# 01-pushbutton_interface.net
KiCad netlist of a schematic drawn in EAGLE
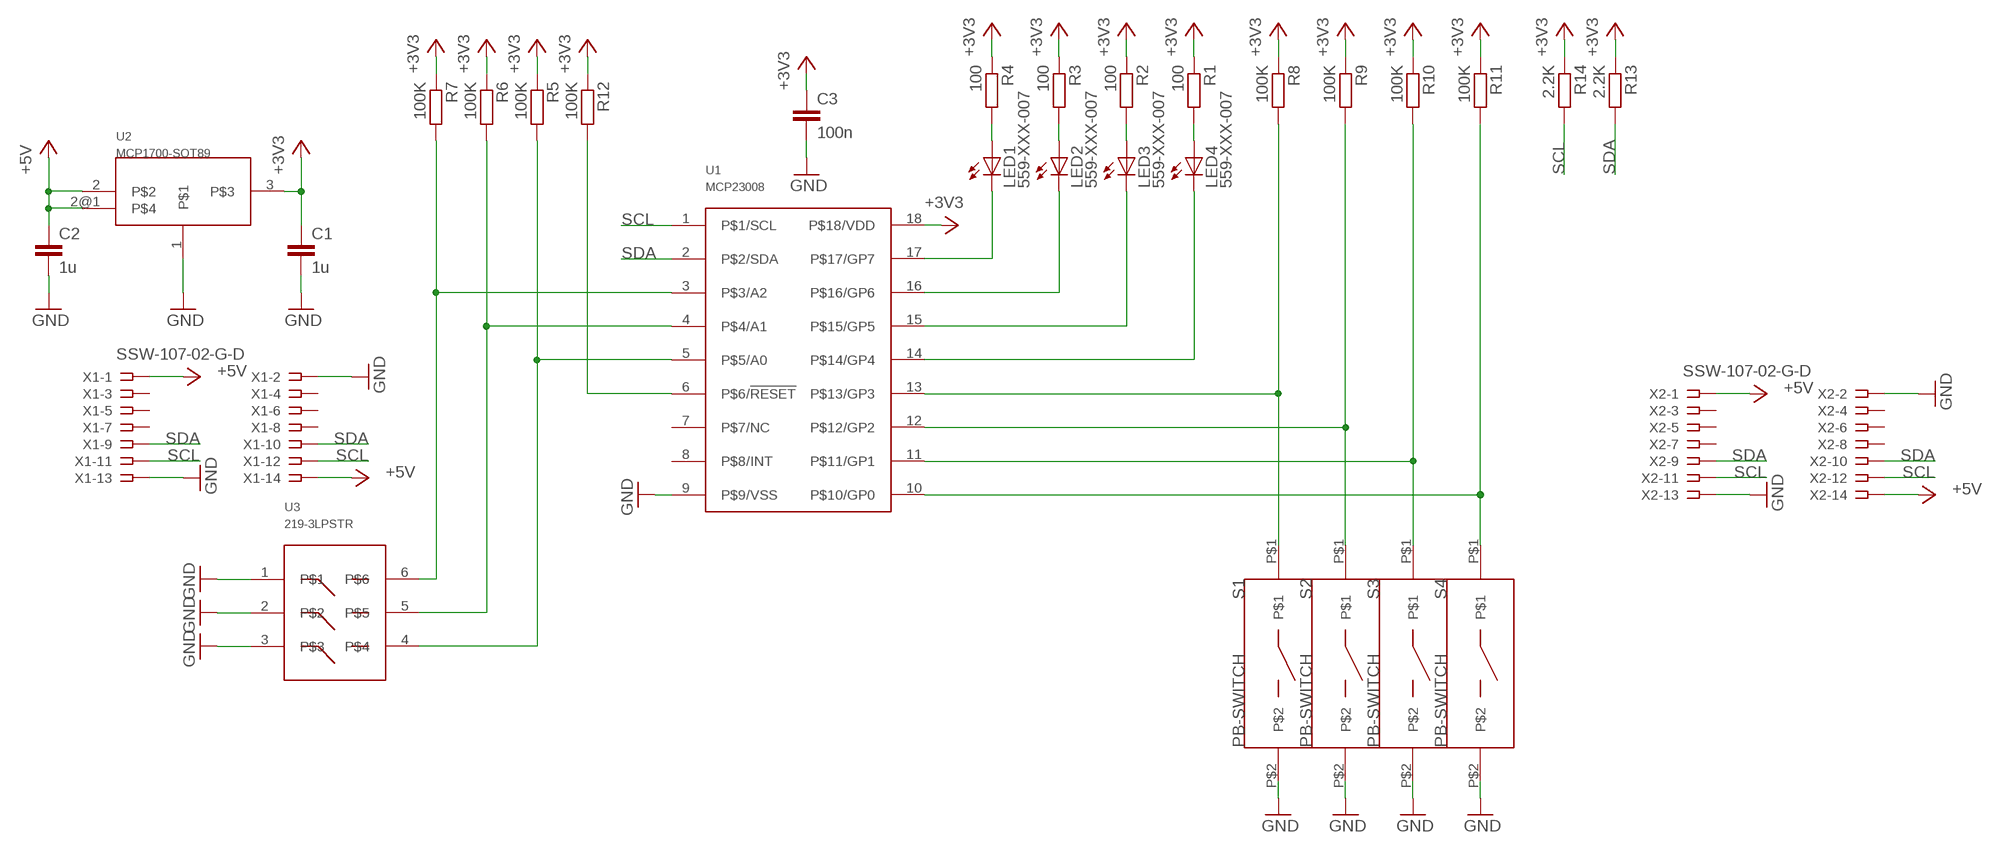
[diagram p0: schematic, sheet 1]

(export (version "E")
  (design (tool "Eeschema 10.0.6"))
  (components
    (comp (ref "C1")
      (value "1u")
      (footprint "eagle-import:C0805")
      (libsource (lib "eagle-import") (part "C-EUC0805"))
    )
    (comp (ref "C2")
      (value "1u")
      (footprint "eagle-import:C0805")
      (libsource (lib "eagle-import") (part "C-EUC0805"))
    )
    (comp (ref "C3")
      (value "100n")
      (footprint "eagle-import:C0805")
      (libsource (lib "eagle-import") (part "C-EUC0805"))
    )
    (comp (ref "LED1")
      (value "559-XXX-007")
      (footprint "eagle-import:LED")
      (libsource (lib "eagle-import") (part "559-XXX-007"))
    )
    (comp (ref "LED2")
      (value "559-XXX-007")
      (footprint "eagle-import:LED")
      (libsource (lib "eagle-import") (part "559-XXX-007"))
    )
    (comp (ref "LED3")
      (value "559-XXX-007")
      (footprint "eagle-import:LED")
      (libsource (lib "eagle-import") (part "559-XXX-007"))
    )
    (comp (ref "LED4")
      (value "559-XXX-007")
      (footprint "eagle-import:LED")
      (libsource (lib "eagle-import") (part "559-XXX-007"))
    )
    (comp (ref "R1")
      (value "100")
      (footprint "eagle-import:R0805")
      (libsource (lib "eagle-import") (part "R-EU_R0805"))
    )
    (comp (ref "R2")
      (value "100")
      (footprint "eagle-import:R0805")
      (libsource (lib "eagle-import") (part "R-EU_R0805"))
    )
    (comp (ref "R3")
      (value "100")
      (footprint "eagle-import:R0805")
      (libsource (lib "eagle-import") (part "R-EU_R0805"))
    )
    (comp (ref "R4")
      (value "100")
      (footprint "eagle-import:R0805")
      (libsource (lib "eagle-import") (part "R-EU_R0805"))
    )
    (comp (ref "R5")
      (value "100K")
      (footprint "eagle-import:R0805")
      (libsource (lib "eagle-import") (part "R-EU_R0805"))
    )
    (comp (ref "R6")
      (value "100K")
      (footprint "eagle-import:R0805")
      (libsource (lib "eagle-import") (part "R-EU_R0805"))
    )
    (comp (ref "R7")
      (value "100K")
      (footprint "eagle-import:R0805")
      (libsource (lib "eagle-import") (part "R-EU_R0805"))
    )
    (comp (ref "R8")
      (value "100K")
      (footprint "eagle-import:R0805")
      (libsource (lib "eagle-import") (part "R-EU_R0805"))
    )
    (comp (ref "R9")
      (value "100K")
      (footprint "eagle-import:R0805")
      (libsource (lib "eagle-import") (part "R-EU_R0805"))
    )
    (comp (ref "R10")
      (value "100K")
      (footprint "eagle-import:R0805")
      (libsource (lib "eagle-import") (part "R-EU_R0805"))
    )
    (comp (ref "R11")
      (value "100K")
      (footprint "eagle-import:R0805")
      (libsource (lib "eagle-import") (part "R-EU_R0805"))
    )
    (comp (ref "R12")
      (value "100K")
      (footprint "eagle-import:R0805")
      (libsource (lib "eagle-import") (part "R-EU_R0805"))
    )
    (comp (ref "R13")
      (value "2.2K")
      (footprint "eagle-import:R0805")
      (libsource (lib "eagle-import") (part "R-EU_R0805"))
    )
    (comp (ref "R14")
      (value "2.2K")
      (footprint "eagle-import:R0805")
      (libsource (lib "eagle-import") (part "R-EU_R0805"))
    )
    (comp (ref "S1")
      (value "PB-SWITCH")
      (footprint "eagle-import:SWITCH")
      (libsource (lib "eagle-import") (part "PB-SWITCH"))
    )
    (comp (ref "S2")
      (value "PB-SWITCH")
      (footprint "eagle-import:SWITCH")
      (libsource (lib "eagle-import") (part "PB-SWITCH"))
    )
    (comp (ref "S3")
      (value "PB-SWITCH")
      (footprint "eagle-import:SWITCH")
      (libsource (lib "eagle-import") (part "PB-SWITCH"))
    )
    (comp (ref "S4")
      (value "PB-SWITCH")
      (footprint "eagle-import:SWITCH")
      (libsource (lib "eagle-import") (part "PB-SWITCH"))
    )
    (comp (ref "U1")
      (value "MCP23008")
      (footprint "eagle-import:MCP23008-SO18")
      (libsource (lib "eagle-import") (part "MCP23008"))
    )
    (comp (ref "U2")
      (value "MCP1700-SOT89")
      (footprint "eagle-import:MCP1700-SOT89")
      (libsource (lib "eagle-import") (part "MCP1700-SOT89"))
    )
    (comp (ref "U3")
      (value "219-3LPSTR")
      (footprint "eagle-import:219-3LPSTR")
      (libsource (lib "eagle-import") (part "219-3LPSTR"))
    )
    (comp (ref "X1")
      (value "SSW-107-02-G-D")
      (footprint "eagle-import:SSW-107-02-G-D")
      (fields (field (name "MF") "Samtec Inc."))
      (libsource (lib "eagle-import") (part "SSW-107-02-G-D"))
    )
    (comp (ref "X2")
      (value "SSW-107-02-G-D")
      (footprint "eagle-import:SSW-107-02-G-D")
      (fields (field (name "MF") "Samtec Inc."))
      (libsource (lib "eagle-import") (part "SSW-107-02-G-D"))
    )
  )
  (nets
    (net (code "1") (name "+3V3") (class "Default")
      (node (ref "C1") (pin "1") (pinfunction "1_1") (pintype "passive"))
      (node (ref "C3") (pin "1") (pinfunction "1_1") (pintype "passive"))
      (node (ref "R1") (pin "1") (pinfunction "1_1") (pintype "passive"))
      (node (ref "R10") (pin "1") (pinfunction "1_1") (pintype "passive"))
      (node (ref "R11") (pin "1") (pinfunction "1_1") (pintype "passive"))
      (node (ref "R12") (pin "1") (pinfunction "1_1") (pintype "passive"))
      (node (ref "R13") (pin "1") (pinfunction "1_1") (pintype "passive"))
      (node (ref "R14") (pin "1") (pinfunction "1_1") (pintype "passive"))
      (node (ref "R2") (pin "1") (pinfunction "1_1") (pintype "passive"))
      (node (ref "R3") (pin "1") (pinfunction "1_1") (pintype "passive"))
      (node (ref "R4") (pin "1") (pinfunction "1_1") (pintype "passive"))
      (node (ref "R5") (pin "1") (pinfunction "1_1") (pintype "passive"))
      (node (ref "R6") (pin "1") (pinfunction "1_1") (pintype "passive"))
      (node (ref "R7") (pin "1") (pinfunction "1_1") (pintype "passive"))
      (node (ref "R8") (pin "1") (pinfunction "1_1") (pintype "passive"))
      (node (ref "R9") (pin "1") (pinfunction "1_1") (pintype "passive"))
      (node (ref "U1") (pin "18") (pinfunction "P$18/VDD_18") (pintype "bidirectional"))
      (node (ref "U2") (pin "3") (pinfunction "P$3_3") (pintype "bidirectional"))
    )
    (net (code "2") (name "+5V") (class "Default")
      (node (ref "C2") (pin "1") (pinfunction "1_1") (pintype "passive"))
      (node (ref "U2") (pin "2") (pinfunction "P$2_2") (pintype "bidirectional"))
      (node (ref "U2") (pin "2@1") (pinfunction "P$4_2@1") (pintype "bidirectional"))
      (node (ref "X1") (pin "1") (pinfunction "1_1") (pintype "passive"))
      (node (ref "X1") (pin "14") (pinfunction "1_14") (pintype "passive"))
      (node (ref "X2") (pin "1") (pinfunction "1_1") (pintype "passive"))
      (node (ref "X2") (pin "14") (pinfunction "1_14") (pintype "passive"))
    )
    (net (code "3") (name "/SCL") (class "Default")
      (node (ref "R14") (pin "2") (pinfunction "2_2") (pintype "passive"))
      (node (ref "U1") (pin "1") (pinfunction "P$1/SCL_1") (pintype "bidirectional"))
      (node (ref "X1") (pin "11") (pinfunction "1_11") (pintype "passive"))
      (node (ref "X1") (pin "12") (pinfunction "1_12") (pintype "passive"))
      (node (ref "X2") (pin "11") (pinfunction "1_11") (pintype "passive"))
      (node (ref "X2") (pin "12") (pinfunction "1_12") (pintype "passive"))
    )
    (net (code "4") (name "/SDA") (class "Default")
      (node (ref "R13") (pin "2") (pinfunction "2_2") (pintype "passive"))
      (node (ref "U1") (pin "2") (pinfunction "P$2/SDA_2") (pintype "bidirectional"))
      (node (ref "X1") (pin "10") (pinfunction "1_10") (pintype "passive"))
      (node (ref "X1") (pin "9") (pinfunction "1_9") (pintype "passive"))
      (node (ref "X2") (pin "10") (pinfunction "1_10") (pintype "passive"))
      (node (ref "X2") (pin "9") (pinfunction "1_9") (pintype "passive"))
    )
    (net (code "5") (name "GND") (class "Default")
      (node (ref "C1") (pin "2") (pinfunction "2_2") (pintype "passive"))
      (node (ref "C2") (pin "2") (pinfunction "2_2") (pintype "passive"))
      (node (ref "C3") (pin "2") (pinfunction "2_2") (pintype "passive"))
      (node (ref "S1") (pin "P$2") (pinfunction "P$2_P$2") (pintype "bidirectional"))
      (node (ref "S2") (pin "P$2") (pinfunction "P$2_P$2") (pintype "bidirectional"))
      (node (ref "S3") (pin "P$2") (pinfunction "P$2_P$2") (pintype "bidirectional"))
      (node (ref "S4") (pin "P$2") (pinfunction "P$2_P$2") (pintype "bidirectional"))
      (node (ref "U1") (pin "9") (pinfunction "P$9/VSS_9") (pintype "bidirectional"))
      (node (ref "U2") (pin "1") (pinfunction "P$1_1") (pintype "bidirectional"))
      (node (ref "U3") (pin "1") (pinfunction "P$1_1") (pintype "bidirectional"))
      (node (ref "U3") (pin "2") (pinfunction "P$2_2") (pintype "bidirectional"))
      (node (ref "U3") (pin "3") (pinfunction "P$3_3") (pintype "bidirectional"))
      (node (ref "X1") (pin "13") (pinfunction "1_13") (pintype "passive"))
      (node (ref "X1") (pin "2") (pinfunction "1_2") (pintype "passive"))
      (node (ref "X2") (pin "13") (pinfunction "1_13") (pintype "passive"))
      (node (ref "X2") (pin "2") (pinfunction "1_2") (pintype "passive"))
    )
    (net (code "6") (name "Net-(LED1-A)") (class "Default")
      (node (ref "LED1") (pin "P$1") (pinfunction "A_P$1") (pintype "passive"))
      (node (ref "R4") (pin "2") (pinfunction "2_2") (pintype "passive"))
    )
    (net (code "7") (name "Net-(LED1-C)") (class "Default")
      (node (ref "LED1") (pin "P$2") (pinfunction "C_P$2") (pintype "passive"))
      (node (ref "U1") (pin "17") (pinfunction "P$17/GP7_17") (pintype "bidirectional"))
    )
    (net (code "8") (name "Net-(LED2-A)") (class "Default")
      (node (ref "LED2") (pin "P$1") (pinfunction "A_P$1") (pintype "passive"))
      (node (ref "R3") (pin "2") (pinfunction "2_2") (pintype "passive"))
    )
    (net (code "9") (name "Net-(LED2-C)") (class "Default")
      (node (ref "LED2") (pin "P$2") (pinfunction "C_P$2") (pintype "passive"))
      (node (ref "U1") (pin "16") (pinfunction "P$16/GP6_16") (pintype "bidirectional"))
    )
    (net (code "10") (name "Net-(LED3-A)") (class "Default")
      (node (ref "LED3") (pin "P$1") (pinfunction "A_P$1") (pintype "passive"))
      (node (ref "R2") (pin "2") (pinfunction "2_2") (pintype "passive"))
    )
    (net (code "11") (name "Net-(LED3-C)") (class "Default")
      (node (ref "LED3") (pin "P$2") (pinfunction "C_P$2") (pintype "passive"))
      (node (ref "U1") (pin "15") (pinfunction "P$15/GP5_15") (pintype "bidirectional"))
    )
    (net (code "12") (name "Net-(LED4-A)") (class "Default")
      (node (ref "LED4") (pin "P$1") (pinfunction "A_P$1") (pintype "passive"))
      (node (ref "R1") (pin "2") (pinfunction "2_2") (pintype "passive"))
    )
    (net (code "13") (name "Net-(LED4-C)") (class "Default")
      (node (ref "LED4") (pin "P$2") (pinfunction "C_P$2") (pintype "passive"))
      (node (ref "U1") (pin "14") (pinfunction "P$14/GP4_14") (pintype "bidirectional"))
    )
    (net (code "14") (name "Net-(U1-P$3{slash}A2)") (class "Default")
      (node (ref "R7") (pin "2") (pinfunction "2_2") (pintype "passive"))
      (node (ref "U1") (pin "3") (pinfunction "P$3/A2_3") (pintype "bidirectional"))
      (node (ref "U3") (pin "6") (pinfunction "P$6_6") (pintype "bidirectional"))
    )
    (net (code "15") (name "Net-(U1-P$4{slash}A1)") (class "Default")
      (node (ref "R6") (pin "2") (pinfunction "2_2") (pintype "passive"))
      (node (ref "U1") (pin "4") (pinfunction "P$4/A1_4") (pintype "bidirectional"))
      (node (ref "U3") (pin "5") (pinfunction "P$5_5") (pintype "bidirectional"))
    )
    (net (code "16") (name "Net-(U1-P$5{slash}A0)") (class "Default")
      (node (ref "R5") (pin "2") (pinfunction "2_2") (pintype "passive"))
      (node (ref "U1") (pin "5") (pinfunction "P$5/A0_5") (pintype "bidirectional"))
      (node (ref "U3") (pin "4") (pinfunction "P$4_4") (pintype "bidirectional"))
    )
    (net (code "17") (name "Net-(U1-P$6{slash}~{RESET})") (class "Default")
      (node (ref "R12") (pin "2") (pinfunction "2_2") (pintype "passive"))
      (node (ref "U1") (pin "6") (pinfunction "P$6/~{RESET}_6") (pintype "bidirectional"))
    )
    (net (code "18") (name "Net-(U1-P$10{slash}GP0)") (class "Default")
      (node (ref "R11") (pin "2") (pinfunction "2_2") (pintype "passive"))
      (node (ref "S4") (pin "P$1") (pinfunction "P$1_P$1") (pintype "bidirectional"))
      (node (ref "U1") (pin "10") (pinfunction "P$10/GP0_10") (pintype "bidirectional"))
    )
    (net (code "19") (name "Net-(U1-P$11{slash}GP1)") (class "Default")
      (node (ref "R10") (pin "2") (pinfunction "2_2") (pintype "passive"))
      (node (ref "S3") (pin "P$1") (pinfunction "P$1_P$1") (pintype "bidirectional"))
      (node (ref "U1") (pin "11") (pinfunction "P$11/GP1_11") (pintype "bidirectional"))
    )
    (net (code "20") (name "Net-(U1-P$12{slash}GP2)") (class "Default")
      (node (ref "R9") (pin "2") (pinfunction "2_2") (pintype "passive"))
      (node (ref "S2") (pin "P$1") (pinfunction "P$1_P$1") (pintype "bidirectional"))
      (node (ref "U1") (pin "12") (pinfunction "P$12/GP2_12") (pintype "bidirectional"))
    )
    (net (code "21") (name "Net-(U1-P$13{slash}GP3)") (class "Default")
      (node (ref "R8") (pin "2") (pinfunction "2_2") (pintype "passive"))
      (node (ref "S1") (pin "P$1") (pinfunction "P$1_P$1") (pintype "bidirectional"))
      (node (ref "U1") (pin "13") (pinfunction "P$13/GP3_13") (pintype "bidirectional"))
    )
    (net (code "22") (name "unconnected-(U1-P$7{slash}NC-Pad7)") (class "Default")
      (node (ref "U1") (pin "7") (pinfunction "P$7/NC_7") (pintype "bidirectional"))
    )
    (net (code "23") (name "unconnected-(U1-P$8{slash}INT-Pad8)") (class "Default")
      (node (ref "U1") (pin "8") (pinfunction "P$8/INT_8") (pintype "bidirectional"))
    )
    (net (code "24") (name "unconnected-(X1H-1-Pad3)") (class "Default")
      (node (ref "X1") (pin "3") (pinfunction "1_3") (pintype "passive"))
    )
    (net (code "25") (name "unconnected-(X1I-1-Pad4)") (class "Default")
      (node (ref "X1") (pin "4") (pinfunction "1_4") (pintype "passive"))
    )
    (net (code "26") (name "unconnected-(X1J-1-Pad5)") (class "Default")
      (node (ref "X1") (pin "5") (pinfunction "1_5") (pintype "passive"))
    )
    (net (code "27") (name "unconnected-(X1K-1-Pad6)") (class "Default")
      (node (ref "X1") (pin "6") (pinfunction "1_6") (pintype "passive"))
    )
    (net (code "28") (name "unconnected-(X1L-1-Pad7)") (class "Default")
      (node (ref "X1") (pin "7") (pinfunction "1_7") (pintype "passive"))
    )
    (net (code "29") (name "unconnected-(X1M-1-Pad8)") (class "Default")
      (node (ref "X1") (pin "8") (pinfunction "1_8") (pintype "passive"))
    )
    (net (code "30") (name "unconnected-(X2H-1-Pad3)") (class "Default")
      (node (ref "X2") (pin "3") (pinfunction "1_3") (pintype "passive"))
    )
    (net (code "31") (name "unconnected-(X2I-1-Pad4)") (class "Default")
      (node (ref "X2") (pin "4") (pinfunction "1_4") (pintype "passive"))
    )
    (net (code "32") (name "unconnected-(X2J-1-Pad5)") (class "Default")
      (node (ref "X2") (pin "5") (pinfunction "1_5") (pintype "passive"))
    )
    (net (code "33") (name "unconnected-(X2K-1-Pad6)") (class "Default")
      (node (ref "X2") (pin "6") (pinfunction "1_6") (pintype "passive"))
    )
    (net (code "34") (name "unconnected-(X2L-1-Pad7)") (class "Default")
      (node (ref "X2") (pin "7") (pinfunction "1_7") (pintype "passive"))
    )
    (net (code "35") (name "unconnected-(X2M-1-Pad8)") (class "Default")
      (node (ref "X2") (pin "8") (pinfunction "1_8") (pintype "passive"))
    )
  )
)
